# SCH_slime-vr_2022-05-18.net
KiCad netlist of a schematic drawn in EasyEDA
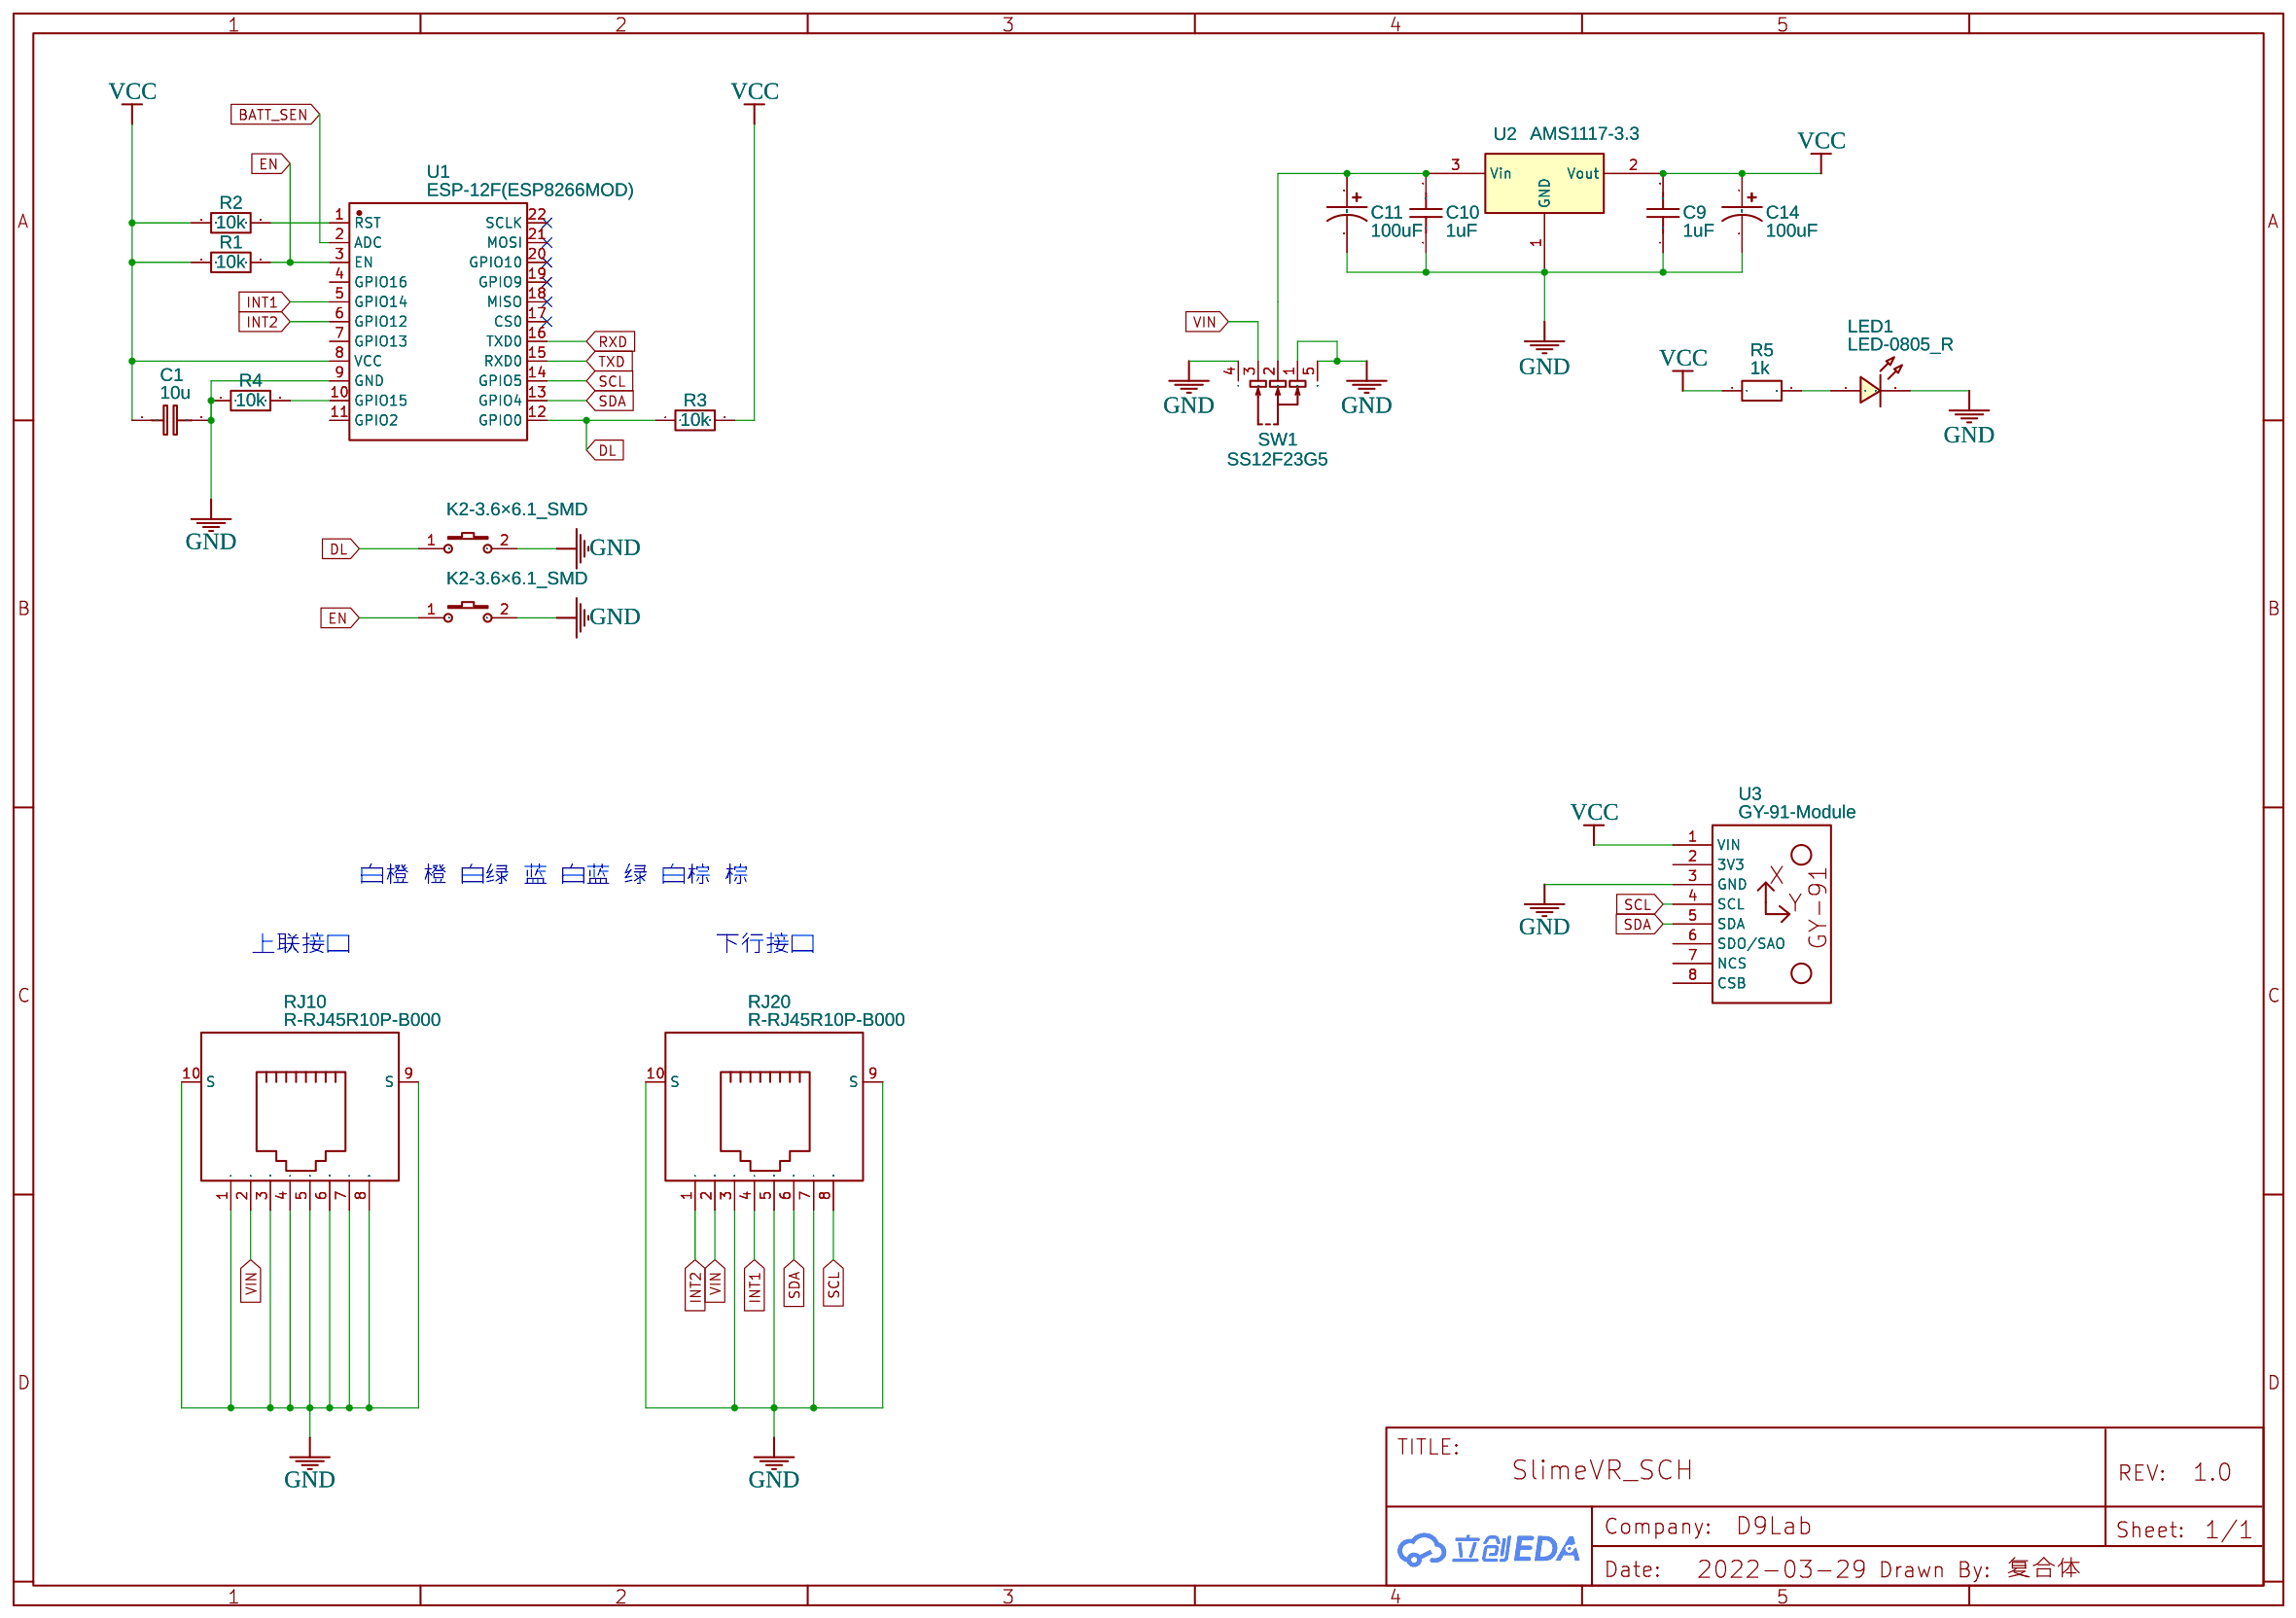
[diagram p0: SlimeVR_SCH]
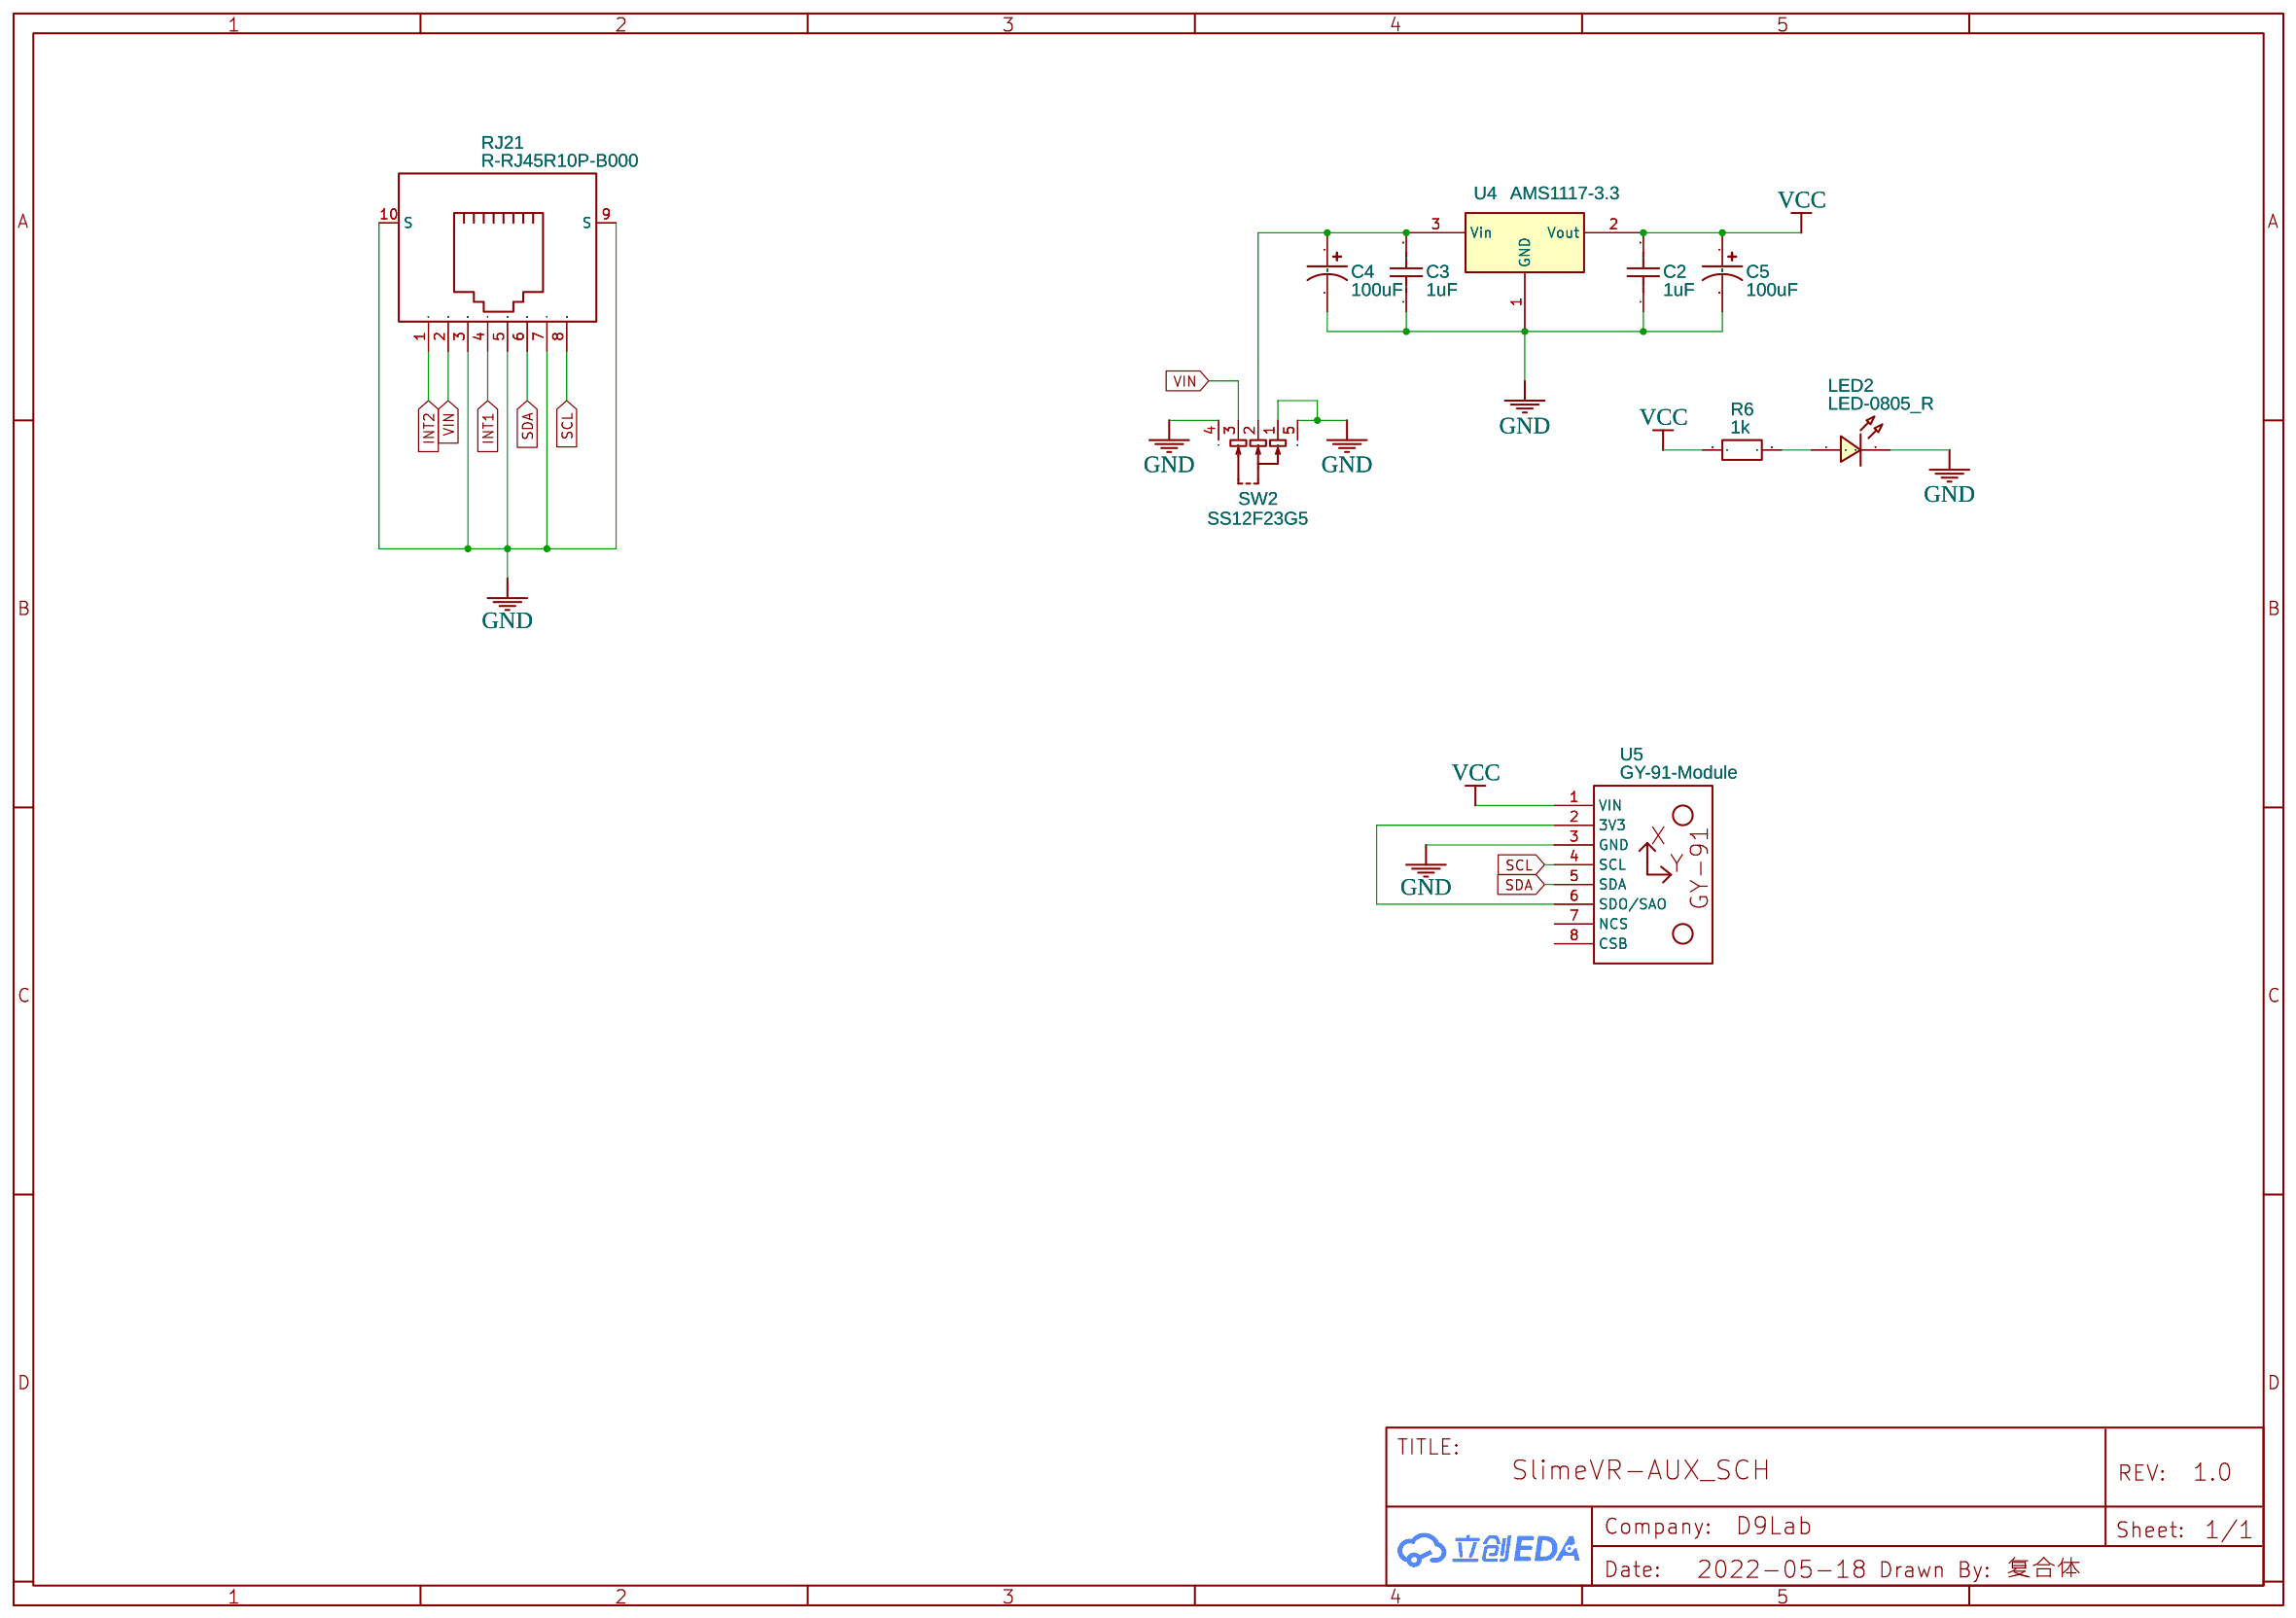
[diagram p1: SlimeVR-AUX_SCH]

(export (version "E")
  (design (tool "Eeschema 10.0.6"))
  (components
    (comp (ref "C1") (value "10u") (libsource (lib "") (part "C_0805_EU")))
    (comp (ref "C9") (value "1uF") (libsource (lib "") (part "C_0603_US")))
    (comp (ref "C10") (value "1uF") (libsource (lib "") (part "C_0603_US")))
    (comp (ref "C11") (value "100uF") (libsource (lib "") (part "C_Tan_SMD_A_US")))
    (comp (ref "C14") (value "100uF") (libsource (lib "") (part "C_Tan_SMD_A_US")))
    (comp (ref "DL")
      (value "K2-3.6×6.1_SMD")
      (fields
        (field (name "BOM_Manufacturer Part") "K2-1107ST-A4SW-06")
        (field (name "BOM_Supplier Part") "C118141")
      )
      (libsource (lib "") (part "K2-3.6×6.1_SMD"))
    )
    (comp (ref "EN")
      (value "K2-3.6×6.1_SMD")
      (fields
        (field (name "BOM_Manufacturer Part") "K2-1107ST-A4SW-06")
        (field (name "BOM_Supplier Part") "C118141")
      )
      (libsource (lib "") (part "K2-3.6×6.1_SMD_1"))
    )
    (comp (ref "LED1")
      (value "LED-0805_R")
      (fields
        (field (name "BOM_Manufacturer Part") "17-21SURC/S530-A3/TR8")
        (field (name "BOM_Supplier Part") "C72037")
      )
      (libsource (lib "") (part "LED-0805_R"))
    )
    (comp (ref "R1") (value "10k") (libsource (lib "") (part "R_0805_EU")))
    (comp (ref "R2") (value "10k") (libsource (lib "") (part "R_0805_EU")))
    (comp (ref "R3") (value "10k") (libsource (lib "") (part "R_0805_EU")))
    (comp (ref "R4") (value "10k") (libsource (lib "") (part "R_0805_EU")))
    (comp (ref "R5") (value "1k") (libsource (lib "") (part "R_0805_EU")))
    (comp (ref "RJ10")
      (value "R-RJ45R10P-B000")
      (fields (field (name "BOM_Supplier Part") "C386758"))
      (libsource (lib "") (part "R-RJ45R10P-B000"))
    )
    (comp (ref "RJ20")
      (value "R-RJ45R10P-B000")
      (fields (field (name "BOM_Supplier Part") "C386758"))
      (libsource (lib "") (part "R-RJ45R10P-B000"))
    )
    (comp (ref "SW1")
      (value "SS12F23G5")
      (fields (field (name "BOM_Supplier Part") "C2887262"))
      (libsource (lib "") (part "SS12F23G5"))
    )
    (comp (ref "U1")
      (value "ESP-12F(ESP8266MOD)")
      (fields (field (name "BOM_Supplier Part") "C82891"))
      (libsource (lib "") (part "ESP-12F(ESP8266MOD)"))
    )
    (comp (ref "U2")
      (value "AMS1117-3.3")
      (fields (field (name "BOM_Manufacturer Part") "?"))
      (libsource (lib "") (part "Unknown_775_-715"))
    )
    (comp (ref "U3")
      (value "GY-91-Module")
      (fields (field (name "BOM_Manufacturer Part") "GY-91 MPU9250 + BMP280"))
      (libsource (lib "") (part "GY-91-Module"))
    )
    (comp (ref "C2") (value "1uF") (libsource (lib "") (part "C_0603_US")))
    (comp (ref "C3") (value "1uF") (libsource (lib "") (part "C_0603_US")))
    (comp (ref "C4") (value "100uF") (libsource (lib "") (part "C_Tan_SMD_A_US")))
    (comp (ref "C5") (value "100uF") (libsource (lib "") (part "C_Tan_SMD_A_US")))
    (comp (ref "LED2")
      (value "LED-0805_R")
      (fields
        (field (name "BOM_Manufacturer Part") "17-21SURC/S530-A3/TR8")
        (field (name "BOM_Supplier Part") "C72037")
      )
      (libsource (lib "") (part "LED-0805_R"))
    )
    (comp (ref "R6") (value "1k") (libsource (lib "") (part "R_0805_EU")))
    (comp (ref "RJ21")
      (value "R-RJ45R10P-B000")
      (fields (field (name "BOM_Supplier Part") "C386758"))
      (libsource (lib "") (part "R-RJ45R10P-B000"))
    )
    (comp (ref "SW2")
      (value "SS12F23G5")
      (fields (field (name "BOM_Supplier Part") "C2887262"))
      (libsource (lib "") (part "SS12F23G5"))
    )
    (comp (ref "U4")
      (value "AMS1117-3.3")
      (fields (field (name "BOM_Manufacturer Part") "?"))
      (libsource (lib "") (part "Unknown_765_-685"))
    )
    (comp (ref "U5")
      (value "GY-91-Module")
      (fields (field (name "BOM_Manufacturer Part") "GY-91 MPU9250 + BMP280"))
      (libsource (lib "") (part "GY-91-Module"))
    )
  )
  (nets
    (net (code "1") (name "BATT_SEN") (class "Default")
      (node (ref "U1") (pin "2") (pinfunction "ADC_2") (pintype "unspecified"))
    )
    (net (code "2") (name "DL") (class "Default")
      (node (ref "DL") (pin "1") (pinfunction "1_1") (pintype "unspecified"))
      (node (ref "R3") (pin "1") (pinfunction "1_1") (pintype "unspecified"))
      (node (ref "U1") (pin "12") (pinfunction "GPIO0_12") (pintype "unspecified"))
    )
    (net (code "3") (name "EN") (class "Default")
      (node (ref "EN") (pin "1") (pinfunction "1_1") (pintype "unspecified"))
      (node (ref "R1") (pin "2") (pinfunction "2_2") (pintype "unspecified"))
      (node (ref "U1") (pin "3") (pinfunction "EN_3") (pintype "unspecified"))
    )
    (net (code "4") (name "GND") (class "Default")
      (node (ref "C1") (pin "2") (pinfunction "2_2") (pintype "unspecified"))
      (node (ref "C10") (pin "1") (pinfunction "1_1") (pintype "unspecified"))
      (node (ref "C11") (pin "2") (pinfunction "2_2") (pintype "unspecified"))
      (node (ref "C14") (pin "2") (pinfunction "2_2") (pintype "unspecified"))
      (node (ref "C2") (pin "1") (pinfunction "1_1") (pintype "unspecified"))
      (node (ref "C3") (pin "1") (pinfunction "1_1") (pintype "unspecified"))
      (node (ref "C4") (pin "2") (pinfunction "2_2") (pintype "unspecified"))
      (node (ref "C5") (pin "2") (pinfunction "2_2") (pintype "unspecified"))
      (node (ref "C9") (pin "1") (pinfunction "1_1") (pintype "unspecified"))
      (node (ref "DL") (pin "2") (pinfunction "2_2") (pintype "unspecified"))
      (node (ref "EN") (pin "2") (pinfunction "2_2") (pintype "unspecified"))
      (node (ref "LED1") (pin "2") (pinfunction "2_2") (pintype "unspecified"))
      (node (ref "LED2") (pin "2") (pinfunction "2_2") (pintype "unspecified"))
      (node (ref "R4") (pin "1") (pinfunction "1_1") (pintype "unspecified"))
      (node (ref "RJ10") (pin "1") (pinfunction "1_1") (pintype "unspecified"))
      (node (ref "RJ10") (pin "10") (pinfunction "S_10") (pintype "unspecified"))
      (node (ref "RJ10") (pin "3") (pinfunction "3_3") (pintype "unspecified"))
      (node (ref "RJ10") (pin "4") (pinfunction "4_4") (pintype "unspecified"))
      (node (ref "RJ10") (pin "5") (pinfunction "5_5") (pintype "unspecified"))
      (node (ref "RJ10") (pin "6") (pinfunction "6_6") (pintype "unspecified"))
      (node (ref "RJ10") (pin "7") (pinfunction "7_7") (pintype "unspecified"))
      (node (ref "RJ10") (pin "8") (pinfunction "8_8") (pintype "unspecified"))
      (node (ref "RJ10") (pin "9") (pinfunction "S_9") (pintype "unspecified"))
      (node (ref "RJ20") (pin "10") (pinfunction "S_10") (pintype "unspecified"))
      (node (ref "RJ20") (pin "3") (pinfunction "3_3") (pintype "unspecified"))
      (node (ref "RJ20") (pin "5") (pinfunction "5_5") (pintype "unspecified"))
      (node (ref "RJ20") (pin "7") (pinfunction "7_7") (pintype "unspecified"))
      (node (ref "RJ20") (pin "9") (pinfunction "S_9") (pintype "unspecified"))
      (node (ref "RJ21") (pin "10") (pinfunction "S_10") (pintype "unspecified"))
      (node (ref "RJ21") (pin "3") (pinfunction "3_3") (pintype "unspecified"))
      (node (ref "RJ21") (pin "5") (pinfunction "5_5") (pintype "unspecified"))
      (node (ref "RJ21") (pin "7") (pinfunction "7_7") (pintype "unspecified"))
      (node (ref "RJ21") (pin "9") (pinfunction "S_9") (pintype "unspecified"))
      (node (ref "SW1") (pin "1") (pinfunction "1_1") (pintype "unspecified"))
      (node (ref "SW1") (pin "4") (pinfunction "4_4") (pintype "unspecified"))
      (node (ref "SW1") (pin "5") (pinfunction "5_5") (pintype "unspecified"))
      (node (ref "SW2") (pin "1") (pinfunction "1_1") (pintype "unspecified"))
      (node (ref "SW2") (pin "4") (pinfunction "4_4") (pintype "unspecified"))
      (node (ref "SW2") (pin "5") (pinfunction "5_5") (pintype "unspecified"))
      (node (ref "U1") (pin "9") (pinfunction "GND_9") (pintype "unspecified"))
      (node (ref "U2") (pin "1") (pinfunction "GND_1") (pintype "unspecified"))
      (node (ref "U3") (pin "3") (pinfunction "GND_3") (pintype "unspecified"))
      (node (ref "U4") (pin "1") (pinfunction "GND_1") (pintype "unspecified"))
      (node (ref "U5") (pin "3") (pinfunction "GND_3") (pintype "unspecified"))
    )
    (net (code "5") (name "INT1") (class "Default")
      (node (ref "RJ20") (pin "4") (pinfunction "4_4") (pintype "unspecified"))
      (node (ref "RJ21") (pin "4") (pinfunction "4_4") (pintype "unspecified"))
      (node (ref "U1") (pin "5") (pinfunction "GPIO14_5") (pintype "unspecified"))
    )
    (net (code "6") (name "INT2") (class "Default")
      (node (ref "RJ20") (pin "1") (pinfunction "1_1") (pintype "unspecified"))
      (node (ref "RJ21") (pin "1") (pinfunction "1_1") (pintype "unspecified"))
      (node (ref "U1") (pin "6") (pinfunction "GPIO12_6") (pintype "unspecified"))
    )
    (net (code "7") (name "Net-(LED1-Pad1)") (class "Default")
      (node (ref "LED1") (pin "1") (pinfunction "1_1") (pintype "unspecified"))
      (node (ref "R5") (pin "2") (pinfunction "2_2") (pintype "unspecified"))
    )
    (net (code "8") (name "Net-(LED2-Pad1)") (class "Default")
      (node (ref "LED2") (pin "1") (pinfunction "1_1") (pintype "unspecified"))
      (node (ref "R6") (pin "2") (pinfunction "2_2") (pintype "unspecified"))
    )
    (net (code "9") (name "Net-(U1-GPIO15)") (class "Default")
      (node (ref "R4") (pin "2") (pinfunction "2_2") (pintype "unspecified"))
      (node (ref "U1") (pin "10") (pinfunction "GPIO15_10") (pintype "unspecified"))
    )
    (net (code "10") (name "Net-(U1-RST)") (class "Default")
      (node (ref "R2") (pin "2") (pinfunction "2_2") (pintype "unspecified"))
      (node (ref "U1") (pin "1") (pinfunction "RST_1") (pintype "unspecified"))
    )
    (net (code "11") (name "Net-(U2-Vin)") (class "Default")
      (node (ref "C10") (pin "2") (pinfunction "2_2") (pintype "unspecified"))
      (node (ref "C11") (pin "1") (pinfunction "1_1") (pintype "unspecified"))
      (node (ref "SW1") (pin "2") (pinfunction "2_2") (pintype "unspecified"))
      (node (ref "U2") (pin "3") (pinfunction "Vin_3") (pintype "unspecified"))
    )
    (net (code "12") (name "Net-(U4-Vin)") (class "Default")
      (node (ref "C3") (pin "2") (pinfunction "2_2") (pintype "unspecified"))
      (node (ref "C4") (pin "1") (pinfunction "1_1") (pintype "unspecified"))
      (node (ref "SW2") (pin "2") (pinfunction "2_2") (pintype "unspecified"))
      (node (ref "U4") (pin "3") (pinfunction "Vin_3") (pintype "unspecified"))
    )
    (net (code "13") (name "Net-(U5-3V3)") (class "Default")
      (node (ref "U5") (pin "2") (pinfunction "3V3_2") (pintype "unspecified"))
      (node (ref "U5") (pin "6") (pinfunction "SDO/SAO_6") (pintype "unspecified"))
    )
    (net (code "14") (name "RXD") (class "Default")
      (node (ref "U1") (pin "16") (pinfunction "TXD0_16") (pintype "unspecified"))
    )
    (net (code "15") (name "SCL") (class "Default")
      (node (ref "RJ20") (pin "8") (pinfunction "8_8") (pintype "unspecified"))
      (node (ref "RJ21") (pin "8") (pinfunction "8_8") (pintype "unspecified"))
      (node (ref "U1") (pin "14") (pinfunction "GPIO5_14") (pintype "unspecified"))
      (node (ref "U3") (pin "4") (pinfunction "SCL_4") (pintype "unspecified"))
      (node (ref "U5") (pin "4") (pinfunction "SCL_4") (pintype "unspecified"))
    )
    (net (code "16") (name "SDA") (class "Default")
      (node (ref "RJ20") (pin "6") (pinfunction "6_6") (pintype "unspecified"))
      (node (ref "RJ21") (pin "6") (pinfunction "6_6") (pintype "unspecified"))
      (node (ref "U1") (pin "13") (pinfunction "GPIO4_13") (pintype "unspecified"))
      (node (ref "U3") (pin "5") (pinfunction "SDA_5") (pintype "unspecified"))
      (node (ref "U5") (pin "5") (pinfunction "SDA_5") (pintype "unspecified"))
    )
    (net (code "17") (name "TXD") (class "Default")
      (node (ref "U1") (pin "15") (pinfunction "RXD0_15") (pintype "unspecified"))
    )
    (net (code "18") (name "VCC") (class "Default")
      (node (ref "C1") (pin "1") (pinfunction "1_1") (pintype "unspecified"))
      (node (ref "C14") (pin "1") (pinfunction "1_1") (pintype "unspecified"))
      (node (ref "C2") (pin "2") (pinfunction "2_2") (pintype "unspecified"))
      (node (ref "C5") (pin "1") (pinfunction "1_1") (pintype "unspecified"))
      (node (ref "C9") (pin "2") (pinfunction "2_2") (pintype "unspecified"))
      (node (ref "R1") (pin "1") (pinfunction "1_1") (pintype "unspecified"))
      (node (ref "R2") (pin "1") (pinfunction "1_1") (pintype "unspecified"))
      (node (ref "R3") (pin "2") (pinfunction "2_2") (pintype "unspecified"))
      (node (ref "R5") (pin "1") (pinfunction "1_1") (pintype "unspecified"))
      (node (ref "R6") (pin "1") (pinfunction "1_1") (pintype "unspecified"))
      (node (ref "U1") (pin "8") (pinfunction "VCC_8") (pintype "unspecified"))
      (node (ref "U2") (pin "2") (pinfunction "Vout_2") (pintype "unspecified"))
      (node (ref "U3") (pin "1") (pinfunction "VIN_1") (pintype "unspecified"))
      (node (ref "U4") (pin "2") (pinfunction "Vout_2") (pintype "unspecified"))
      (node (ref "U5") (pin "1") (pinfunction "VIN_1") (pintype "unspecified"))
    )
    (net (code "19") (name "VIN") (class "Default")
      (node (ref "RJ10") (pin "2") (pinfunction "2_2") (pintype "unspecified"))
      (node (ref "RJ20") (pin "2") (pinfunction "2_2") (pintype "unspecified"))
      (node (ref "RJ21") (pin "2") (pinfunction "2_2") (pintype "unspecified"))
      (node (ref "SW1") (pin "3") (pinfunction "3_3") (pintype "unspecified"))
      (node (ref "SW2") (pin "3") (pinfunction "3_3") (pintype "unspecified"))
    )
    (net (code "20") (name "unconnected-(U1-CS0-Pad17)") (class "Default")
      (node (ref "U1") (pin "17") (pinfunction "CS0_17") (pintype "unspecified+no_connect"))
    )
    (net (code "21") (name "unconnected-(U1-GPIO2-Pad11)") (class "Default")
      (node (ref "U1") (pin "11") (pinfunction "GPIO2_11") (pintype "unspecified"))
    )
    (net (code "22") (name "unconnected-(U1-GPIO9-Pad19)") (class "Default")
      (node (ref "U1") (pin "19") (pinfunction "GPIO9_19") (pintype "unspecified+no_connect"))
    )
    (net (code "23") (name "unconnected-(U1-GPIO10-Pad20)") (class "Default")
      (node (ref "U1") (pin "20") (pinfunction "GPIO10_20") (pintype "unspecified+no_connect"))
    )
    (net (code "24") (name "unconnected-(U1-GPIO13-Pad7)") (class "Default")
      (node (ref "U1") (pin "7") (pinfunction "GPIO13_7") (pintype "unspecified"))
    )
    (net (code "25") (name "unconnected-(U1-GPIO16-Pad4)") (class "Default")
      (node (ref "U1") (pin "4") (pinfunction "GPIO16_4") (pintype "unspecified"))
    )
    (net (code "26") (name "unconnected-(U1-MISO-Pad18)") (class "Default")
      (node (ref "U1") (pin "18") (pinfunction "MISO_18") (pintype "unspecified+no_connect"))
    )
    (net (code "27") (name "unconnected-(U1-MOSI-Pad21)") (class "Default")
      (node (ref "U1") (pin "21") (pinfunction "MOSI_21") (pintype "unspecified+no_connect"))
    )
    (net (code "28") (name "unconnected-(U1-SCLK-Pad22)") (class "Default")
      (node (ref "U1") (pin "22") (pinfunction "SCLK_22") (pintype "unspecified+no_connect"))
    )
    (net (code "29") (name "unconnected-(U3-3V3-Pad2)") (class "Default")
      (node (ref "U3") (pin "2") (pinfunction "3V3_2") (pintype "unspecified"))
    )
    (net (code "30") (name "unconnected-(U3-CSB-Pad8)") (class "Default")
      (node (ref "U3") (pin "8") (pinfunction "CSB_8") (pintype "unspecified"))
    )
    (net (code "31") (name "unconnected-(U3-NCS-Pad7)") (class "Default")
      (node (ref "U3") (pin "7") (pinfunction "NCS_7") (pintype "unspecified"))
    )
    (net (code "32") (name "unconnected-(U3-SDO{slash}SAO-Pad6)") (class "Default")
      (node (ref "U3") (pin "6") (pinfunction "SDO/SAO_6") (pintype "unspecified"))
    )
    (net (code "33") (name "unconnected-(U5-CSB-Pad8)") (class "Default")
      (node (ref "U5") (pin "8") (pinfunction "CSB_8") (pintype "unspecified"))
    )
    (net (code "34") (name "unconnected-(U5-NCS-Pad7)") (class "Default")
      (node (ref "U5") (pin "7") (pinfunction "NCS_7") (pintype "unspecified"))
    )
  )
)
